# main_indoor_sensor.net
KiCad netlist of a schematic drawn in EAGLE
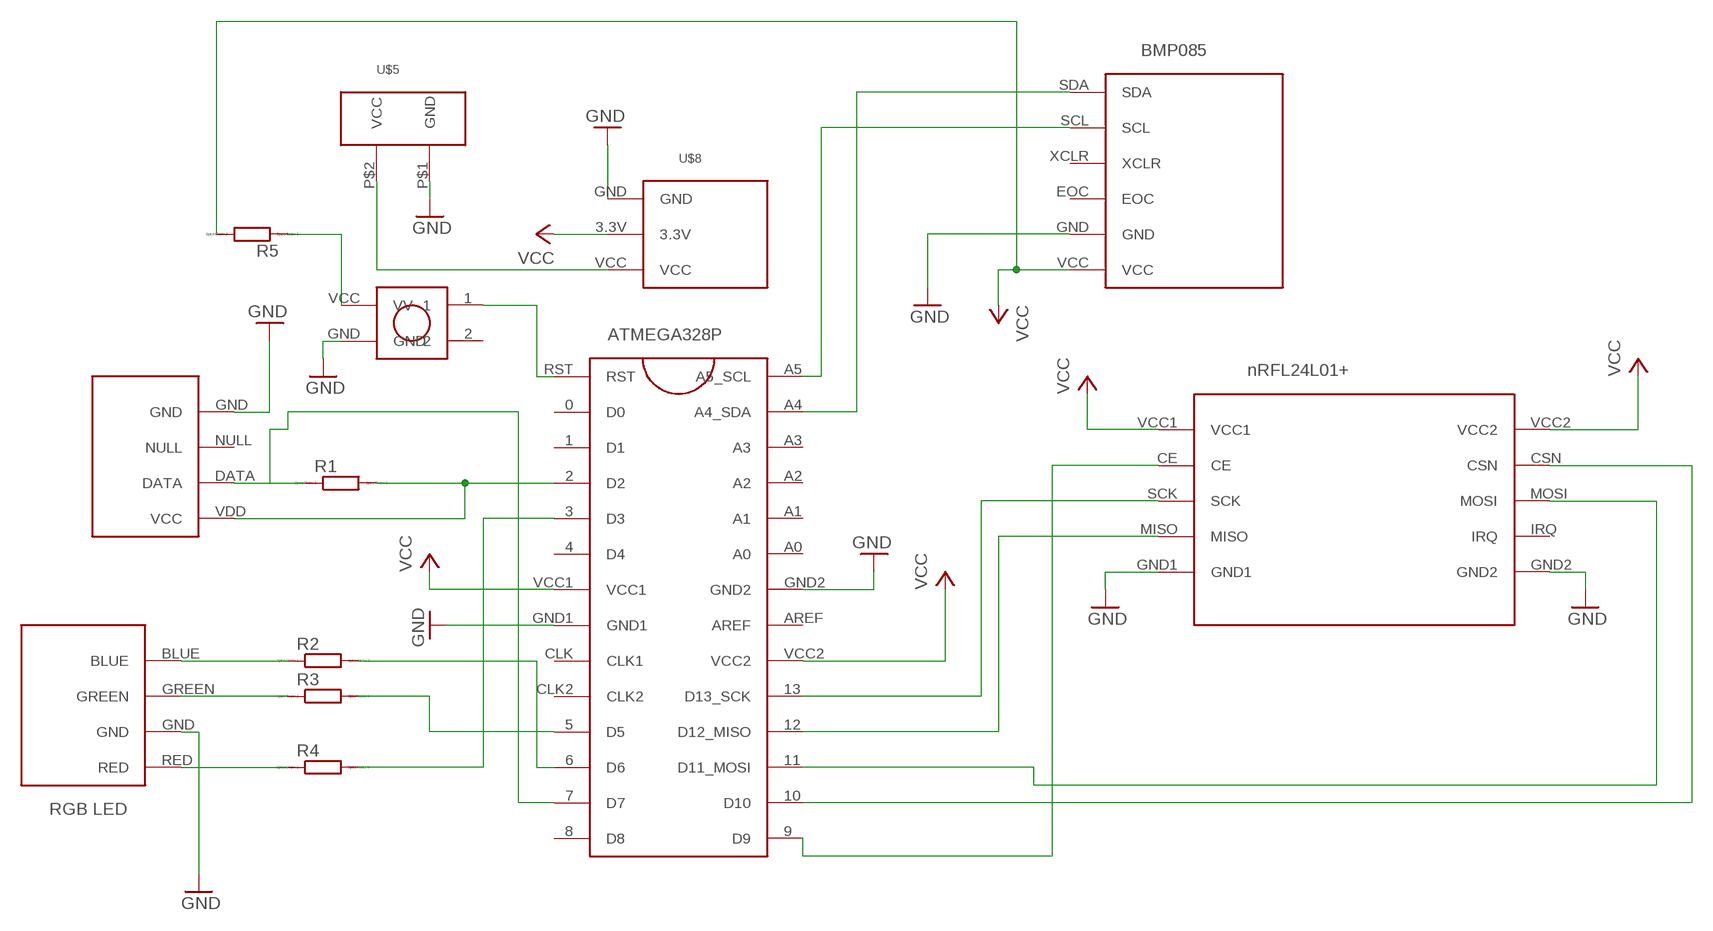
[diagram p0: schematic, sheet 1]

(export (version "E")
  (design (tool "Eeschema 10.0.6"))
  (components
    (comp (ref "R1")
      (value "R0204/7")
      (footprint "eagle-import:0204_7")
      (libsource (lib "eagle-import") (part "R0204/7"))
    )
    (comp (ref "R2")
      (value "R0204/7")
      (footprint "eagle-import:0204_7")
      (libsource (lib "eagle-import") (part "R0204/7"))
    )
    (comp (ref "R3")
      (value "R0204/7")
      (footprint "eagle-import:0204_7")
      (libsource (lib "eagle-import") (part "R0204/7"))
    )
    (comp (ref "R4")
      (value "R0204/7")
      (footprint "eagle-import:0204_7")
      (libsource (lib "eagle-import") (part "R0204/7"))
    )
    (comp (ref "R5")
      (value "R0204/7")
      (footprint "eagle-import:0204_7")
      (libsource (lib "eagle-import") (part "R0204/7"))
    )
    (comp (ref "U$1")
      (value "ATMEGA328PARDUINO")
      (footprint "eagle-import:ATMEGA328P")
      (libsource (lib "eagle-import") (part "ATMEGA328PARDUINO"))
    )
    (comp (ref "U$2")
      (value "BMP085SPARKFUN")
      (footprint "eagle-import:BMP085")
      (libsource (lib "eagle-import") (part "BMP085SPARKFUN"))
    )
    (comp (ref "U$3")
      (value "DHT22WHITE")
      (footprint "eagle-import:DHT22")
      (libsource (lib "eagle-import") (part "DHT22WHITE"))
    )
    (comp (ref "U$4")
      (value "NRF24L0110PINS")
      (footprint "eagle-import:NRF24L01")
      (libsource (lib "eagle-import") (part "NRF24L0110PINS"))
    )
    (comp (ref "U$5")
      (value "2PINCONNECTORSIMPLE")
      (footprint "eagle-import:2PINCONNECTOR")
      (libsource (lib "eagle-import") (part "2PINCONNECTORSIMPLE"))
    )
    (comp (ref "U$6")
      (value "RGB_LED5MM")
      (footprint "eagle-import:RGB_LED")
      (libsource (lib "eagle-import") (part "RGB_LED5MM"))
    )
    (comp (ref "U$7")
      (value "KRS0612PUSH")
      (footprint "eagle-import:KRS0612")
      (libsource (lib "eagle-import") (part "KRS0612PUSH"))
    )
    (comp (ref "U$8")
      (value "NCP1402SPARKFUN")
      (footprint "eagle-import:NCP1402")
      (libsource (lib "eagle-import") (part "NCP1402SPARKFUN"))
    )
  )
  (nets
    (net (code "1") (name "GND") (class "Default")
      (node (ref "U$1") (pin "GND1") (pinfunction "GND1_GND1") (pintype "bidirectional"))
      (node (ref "U$1") (pin "GND2") (pinfunction "GND2_GND2") (pintype "bidirectional"))
      (node (ref "U$2") (pin "GND") (pinfunction "GND_GND") (pintype "bidirectional"))
      (node (ref "U$3") (pin "GND") (pinfunction "GND_GND") (pintype "bidirectional"))
      (node (ref "U$4") (pin "GND1") (pinfunction "GND1_GND1") (pintype "bidirectional"))
      (node (ref "U$4") (pin "GND2") (pinfunction "GND2_GND2") (pintype "bidirectional"))
      (node (ref "U$5") (pin "P$1") (pinfunction "GND_P$1") (pintype "bidirectional"))
      (node (ref "U$6") (pin "GND") (pinfunction "GND_GND") (pintype "bidirectional"))
      (node (ref "U$7") (pin "GND") (pinfunction "GND_GND") (pintype "bidirectional"))
      (node (ref "U$8") (pin "GND") (pinfunction "GND_GND") (pintype "bidirectional"))
    )
    (net (code "2") (name "Net-(R2-Pad1)") (class "Default")
      (node (ref "R2") (pin "1") (pinfunction "1_1") (pintype "passive"))
      (node (ref "U$6") (pin "BLUE") (pinfunction "BLUE_BLUE") (pintype "bidirectional"))
    )
    (net (code "3") (name "Net-(R3-Pad1)") (class "Default")
      (node (ref "R3") (pin "1") (pinfunction "1_1") (pintype "passive"))
      (node (ref "U$6") (pin "GREEN") (pinfunction "GREEN_GREEN") (pintype "bidirectional"))
    )
    (net (code "4") (name "Net-(R4-Pad1)") (class "Default")
      (node (ref "R4") (pin "1") (pinfunction "1_1") (pintype "passive"))
      (node (ref "U$6") (pin "RED") (pinfunction "RED_RED") (pintype "bidirectional"))
    )
    (net (code "5") (name "Net-(U$1-A4_SDA)") (class "Default")
      (node (ref "U$1") (pin "A4") (pinfunction "A4_SDA_A4") (pintype "bidirectional"))
      (node (ref "U$2") (pin "SDA") (pinfunction "SDA_SDA") (pintype "bidirectional"))
    )
    (net (code "6") (name "Net-(U$1-A5_SCL)") (class "Default")
      (node (ref "U$1") (pin "A5") (pinfunction "A5_SCL_A5") (pintype "bidirectional"))
      (node (ref "U$2") (pin "SCL") (pinfunction "SCL_SCL") (pintype "bidirectional"))
    )
    (net (code "7") (name "Net-(U$1-D2)") (class "Default")
      (node (ref "R1") (pin "2") (pinfunction "2_2") (pintype "passive"))
      (node (ref "U$1") (pin "2") (pinfunction "D2_2") (pintype "bidirectional"))
      (node (ref "U$3") (pin "VDD") (pinfunction "VCC_VDD") (pintype "bidirectional"))
    )
    (net (code "8") (name "Net-(U$1-D3)") (class "Default")
      (node (ref "R4") (pin "2") (pinfunction "2_2") (pintype "passive"))
      (node (ref "U$1") (pin "3") (pinfunction "D3_3") (pintype "bidirectional"))
    )
    (net (code "9") (name "Net-(U$1-D5)") (class "Default")
      (node (ref "R3") (pin "2") (pinfunction "2_2") (pintype "passive"))
      (node (ref "U$1") (pin "5") (pinfunction "D5_5") (pintype "bidirectional"))
    )
    (net (code "10") (name "Net-(U$1-D6)") (class "Default")
      (node (ref "R2") (pin "2") (pinfunction "2_2") (pintype "passive"))
      (node (ref "U$1") (pin "6") (pinfunction "D6_6") (pintype "bidirectional"))
    )
    (net (code "11") (name "Net-(U$1-D7)") (class "Default")
      (node (ref "R1") (pin "1") (pinfunction "1_1") (pintype "passive"))
      (node (ref "U$1") (pin "7") (pinfunction "D7_7") (pintype "bidirectional"))
      (node (ref "U$3") (pin "DATA") (pinfunction "DATA_DATA") (pintype "bidirectional"))
    )
    (net (code "12") (name "Net-(U$1-D9)") (class "Default")
      (node (ref "U$1") (pin "9") (pinfunction "D9_9") (pintype "bidirectional"))
      (node (ref "U$4") (pin "CE") (pinfunction "CE_CE") (pintype "bidirectional"))
    )
    (net (code "13") (name "Net-(U$1-D10)") (class "Default")
      (node (ref "U$1") (pin "10") (pinfunction "D10_10") (pintype "bidirectional"))
      (node (ref "U$4") (pin "CSN") (pinfunction "CSN_CSN") (pintype "bidirectional"))
    )
    (net (code "14") (name "Net-(U$1-D11_MOSI)") (class "Default")
      (node (ref "U$1") (pin "11") (pinfunction "D11_MOSI_11") (pintype "bidirectional"))
      (node (ref "U$4") (pin "MOSI") (pinfunction "MOSI_MOSI") (pintype "bidirectional"))
    )
    (net (code "15") (name "Net-(U$1-D12_MISO)") (class "Default")
      (node (ref "U$1") (pin "12") (pinfunction "D12_MISO_12") (pintype "bidirectional"))
      (node (ref "U$4") (pin "MISO") (pinfunction "MISO_MISO") (pintype "bidirectional"))
    )
    (net (code "16") (name "Net-(U$1-D13_SCK)") (class "Default")
      (node (ref "U$1") (pin "13") (pinfunction "D13_SCK_13") (pintype "bidirectional"))
      (node (ref "U$4") (pin "SCK") (pinfunction "SCK_SCK") (pintype "bidirectional"))
    )
    (net (code "17") (name "Net-(U$1-PadRST)") (class "Default")
      (node (ref "U$1") (pin "RST") (pinfunction "RST_RST") (pintype "bidirectional"))
      (node (ref "U$7") (pin "1") (pinfunction "1_1") (pintype "bidirectional"))
    )
    (net (code "18") (name "Net-(U$5-VCC)") (class "Default")
      (node (ref "U$5") (pin "P$2") (pinfunction "VCC_P$2") (pintype "bidirectional"))
      (node (ref "U$8") (pin "VCC") (pinfunction "VCC_VCC") (pintype "bidirectional"))
    )
    (net (code "19") (name "Net-(U$7-VV)") (class "Default")
      (node (ref "R5") (pin "1") (pinfunction "1_1") (pintype "passive"))
      (node (ref "U$7") (pin "VCC") (pinfunction "VV_VCC") (pintype "bidirectional"))
    )
    (net (code "20") (name "VCC") (class "Default")
      (node (ref "R5") (pin "2") (pinfunction "2_2") (pintype "passive"))
      (node (ref "U$1") (pin "VCC1") (pinfunction "VCC1_VCC1") (pintype "bidirectional"))
      (node (ref "U$1") (pin "VCC2") (pinfunction "VCC2_VCC2") (pintype "bidirectional"))
      (node (ref "U$2") (pin "VCC") (pinfunction "VCC_VCC") (pintype "bidirectional"))
      (node (ref "U$4") (pin "VCC1") (pinfunction "VCC1_VCC1") (pintype "bidirectional"))
      (node (ref "U$4") (pin "VCC2") (pinfunction "VCC2_VCC2") (pintype "bidirectional"))
      (node (ref "U$8") (pin "3.3V") (pinfunction "3.3V_3.3V") (pintype "bidirectional"))
    )
    (net (code "21") (name "unconnected-(U$1-CLK1-PadCLK)") (class "Default")
      (node (ref "U$1") (pin "CLK") (pinfunction "CLK1_CLK") (pintype "bidirectional"))
    )
    (net (code "22") (name "unconnected-(U$1-D0-Pad0)") (class "Default")
      (node (ref "U$1") (pin "0") (pinfunction "D0_0") (pintype "bidirectional"))
    )
    (net (code "23") (name "unconnected-(U$1-D1-Pad1)") (class "Default")
      (node (ref "U$1") (pin "1") (pinfunction "D1_1") (pintype "bidirectional"))
    )
    (net (code "24") (name "unconnected-(U$1-D4-Pad4)") (class "Default")
      (node (ref "U$1") (pin "4") (pinfunction "D4_4") (pintype "bidirectional"))
    )
    (net (code "25") (name "unconnected-(U$1-D8-Pad8)") (class "Default")
      (node (ref "U$1") (pin "8") (pinfunction "D8_8") (pintype "bidirectional"))
    )
    (net (code "26") (name "unconnected-(U$1-PadA0)") (class "Default")
      (node (ref "U$1") (pin "A0") (pinfunction "A0_A0") (pintype "bidirectional"))
    )
    (net (code "27") (name "unconnected-(U$1-PadA1)") (class "Default")
      (node (ref "U$1") (pin "A1") (pinfunction "A1_A1") (pintype "bidirectional"))
    )
    (net (code "28") (name "unconnected-(U$1-PadA2)") (class "Default")
      (node (ref "U$1") (pin "A2") (pinfunction "A2_A2") (pintype "bidirectional"))
    )
    (net (code "29") (name "unconnected-(U$1-PadA3)") (class "Default")
      (node (ref "U$1") (pin "A3") (pinfunction "A3_A3") (pintype "bidirectional"))
    )
    (net (code "30") (name "unconnected-(U$1-PadAREF)") (class "Default")
      (node (ref "U$1") (pin "AREF") (pinfunction "AREF_AREF") (pintype "bidirectional"))
    )
    (net (code "31") (name "unconnected-(U$1-PadCLK2)") (class "Default")
      (node (ref "U$1") (pin "CLK2") (pinfunction "CLK2_CLK2") (pintype "bidirectional"))
    )
    (net (code "32") (name "unconnected-(U$2-PadEOC)") (class "Default")
      (node (ref "U$2") (pin "EOC") (pinfunction "EOC_EOC") (pintype "bidirectional"))
    )
    (net (code "33") (name "unconnected-(U$2-PadXCLR)") (class "Default")
      (node (ref "U$2") (pin "XCLR") (pinfunction "XCLR_XCLR") (pintype "bidirectional"))
    )
    (net (code "34") (name "unconnected-(U$3-PadNULL)") (class "Default")
      (node (ref "U$3") (pin "NULL") (pinfunction "NULL_NULL") (pintype "bidirectional"))
    )
    (net (code "35") (name "unconnected-(U$4-PadIRQ)") (class "Default")
      (node (ref "U$4") (pin "IRQ") (pinfunction "IRQ_IRQ") (pintype "bidirectional"))
    )
    (net (code "36") (name "unconnected-(U$7-Pad2)") (class "Default")
      (node (ref "U$7") (pin "2") (pinfunction "2_2") (pintype "bidirectional"))
    )
  )
)
